# GSM.net
KiCad netlist of a schematic drawn in Altium Designer
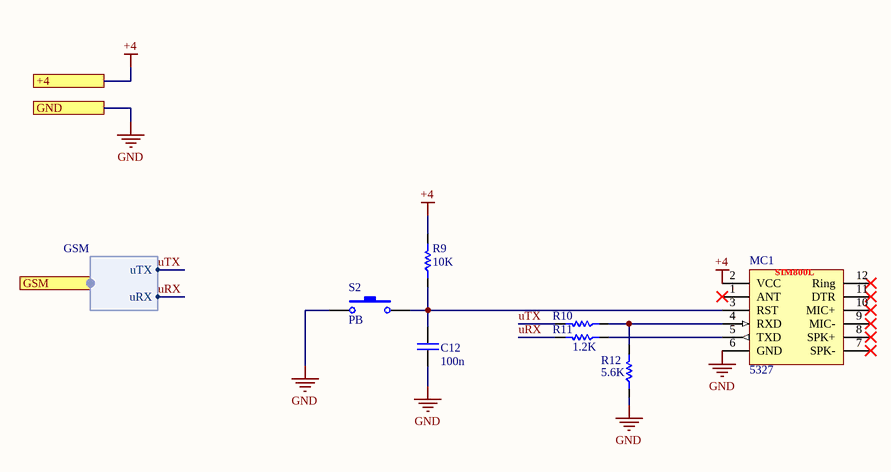
[diagram p0: GSM.SchDoc]

(export (version "E")
  (design (tool "Eeschema 10.0.6"))
  (components
    (comp (ref "C12")
      (value "100n")
      (footprint "CAP 1206/3216")
      (description "Bipolar ceramic capacitor SMD")
      (fields (field (name "VALIDATION") "Valid"))
      (libsource (lib "aKaReZa") (part "Cap_Multi_SMD_100nF_1206"))
    )
    (comp (ref "MC1")
      (value "Sim800L")
      (footprint "Sim800L_Module")
      (description "SimCom GSM/GPRS Module")
      (fields (field (name "INFLOW") "5327") (field (name "VALIDATION") "NT"))
      (libsource (lib "aKaReZa") (part "ModSen_Com_Sim800L"))
    )
    (comp (ref "R9")
      (value "10K")
      (footprint "RES 1206 (3216X08L)")
      (description "Resistor")
      (fields (field (name "VALIDATION") "Valid"))
      (libsource (lib "aKaReZa") (part "Res_SMD_1206"))
    )
    (comp (ref "R10")
      (value "47K")
      (footprint "RES 1206 (3216X08L)")
      (description "Resistor")
      (fields (field (name "VALIDATION") "Valid"))
      (libsource (lib "aKaReZa") (part "Res_SMD_1206"))
    )
    (comp (ref "R11")
      (value "1.2K")
      (footprint "RES 1206 (3216X08L)")
      (description "Resistor")
      (fields (field (name "VALIDATION") "Valid"))
      (libsource (lib "aKaReZa") (part "Res_SMD_1206"))
    )
    (comp (ref "R12")
      (value "5.6K")
      (footprint "RES 1206 (3216X08L)")
      (description "Resistor")
      (fields (field (name "VALIDATION") "Valid"))
      (libsource (lib "aKaReZa") (part "Res_SMD_1206"))
    )
    (comp (ref "S2")
      (value "PB")
      (footprint "SW_PB_SMD_2PIN_SPST_6X3X2")
      (description "SMT Tactile ‎Switch")
      (fields (field (name "VALIDATION") "Valid"))
      (libsource (lib "aKaReZa") (part "SW_PushButton_2_SMD"))
    )
  )
  (nets
    (net (code "2") (name "+4") (class "Default")
      (node (ref "MC1") (pin "2") (pinfunction "VCC_2") (pintype "power_in"))
      (node (ref "R9") (pin "2") (pinfunction "2_2") (pintype "passive"))
    )
    (net (code "3") (name "/uRX") (class "Default")
      (node (ref "R11") (pin "2") (pinfunction "2_2") (pintype "passive"))
    )
    (net (code "4") (name "/uTX") (class "Default")
      (node (ref "R10") (pin "2") (pinfunction "2_2") (pintype "passive"))
    )
    (net (code "6") (name "GND") (class "Default")
      (node (ref "C12") (pin "2") (pinfunction "2_2") (pintype "passive"))
      (node (ref "MC1") (pin "6") (pinfunction "GND_6") (pintype "power_in"))
      (node (ref "R12") (pin "1") (pinfunction "1_1") (pintype "passive"))
      (node (ref "S2") (pin "2") (pinfunction "2_2") (pintype "passive"))
    )
    (net (code "7") (name "Net-(MC1-RST)") (class "Default")
      (node (ref "C12") (pin "1") (pinfunction "1_1") (pintype "passive"))
      (node (ref "MC1") (pin "3") (pinfunction "RST_3") (pintype "passive"))
      (node (ref "R9") (pin "1") (pinfunction "1_1") (pintype "passive"))
      (node (ref "S2") (pin "1") (pinfunction "1_1") (pintype "passive"))
    )
    (net (code "8") (name "Net-(MC1-RXD)") (class "Default")
      (node (ref "MC1") (pin "4") (pinfunction "RXD_4") (pintype "input"))
      (node (ref "R10") (pin "1") (pinfunction "1_1") (pintype "passive"))
      (node (ref "R12") (pin "2") (pinfunction "2_2") (pintype "passive"))
    )
    (net (code "9") (name "Net-(MC1-TXD)") (class "Default")
      (node (ref "MC1") (pin "5") (pinfunction "TXD_5") (pintype "output"))
      (node (ref "R11") (pin "1") (pinfunction "1_1") (pintype "passive"))
    )
    (net (code "10") (name "unconnected-(MC1-ANT-Pad1)") (class "Default")
      (node (ref "MC1") (pin "1") (pinfunction "ANT_1") (pintype "passive+no_connect"))
    )
    (net (code "11") (name "unconnected-(MC1-DTR-Pad11)") (class "Default")
      (node (ref "MC1") (pin "11") (pinfunction "DTR_11") (pintype "passive+no_connect"))
    )
    (net (code "12") (name "unconnected-(MC1-MIC+-Pad10)") (class "Default")
      (node (ref "MC1") (pin "10") (pinfunction "MIC+_10") (pintype "passive+no_connect"))
    )
    (net (code "13") (name "unconnected-(MC1-MIC--Pad9)") (class "Default")
      (node (ref "MC1") (pin "9") (pinfunction "MIC-_9") (pintype "passive+no_connect"))
    )
    (net (code "14") (name "unconnected-(MC1-Ring-Pad12)") (class "Default")
      (node (ref "MC1") (pin "12") (pinfunction "Ring_12") (pintype "passive+no_connect"))
    )
    (net (code "15") (name "unconnected-(MC1-SPK+-Pad8)") (class "Default")
      (node (ref "MC1") (pin "8") (pinfunction "SPK+_8") (pintype "passive+no_connect"))
    )
    (net (code "16") (name "unconnected-(MC1-SPK--Pad7)") (class "Default")
      (node (ref "MC1") (pin "7") (pinfunction "SPK-_7") (pintype "passive+no_connect"))
    )
  )
)
